# HSTF_SMD_V20.net
KiCad netlist of a schematic drawn in EAGLE
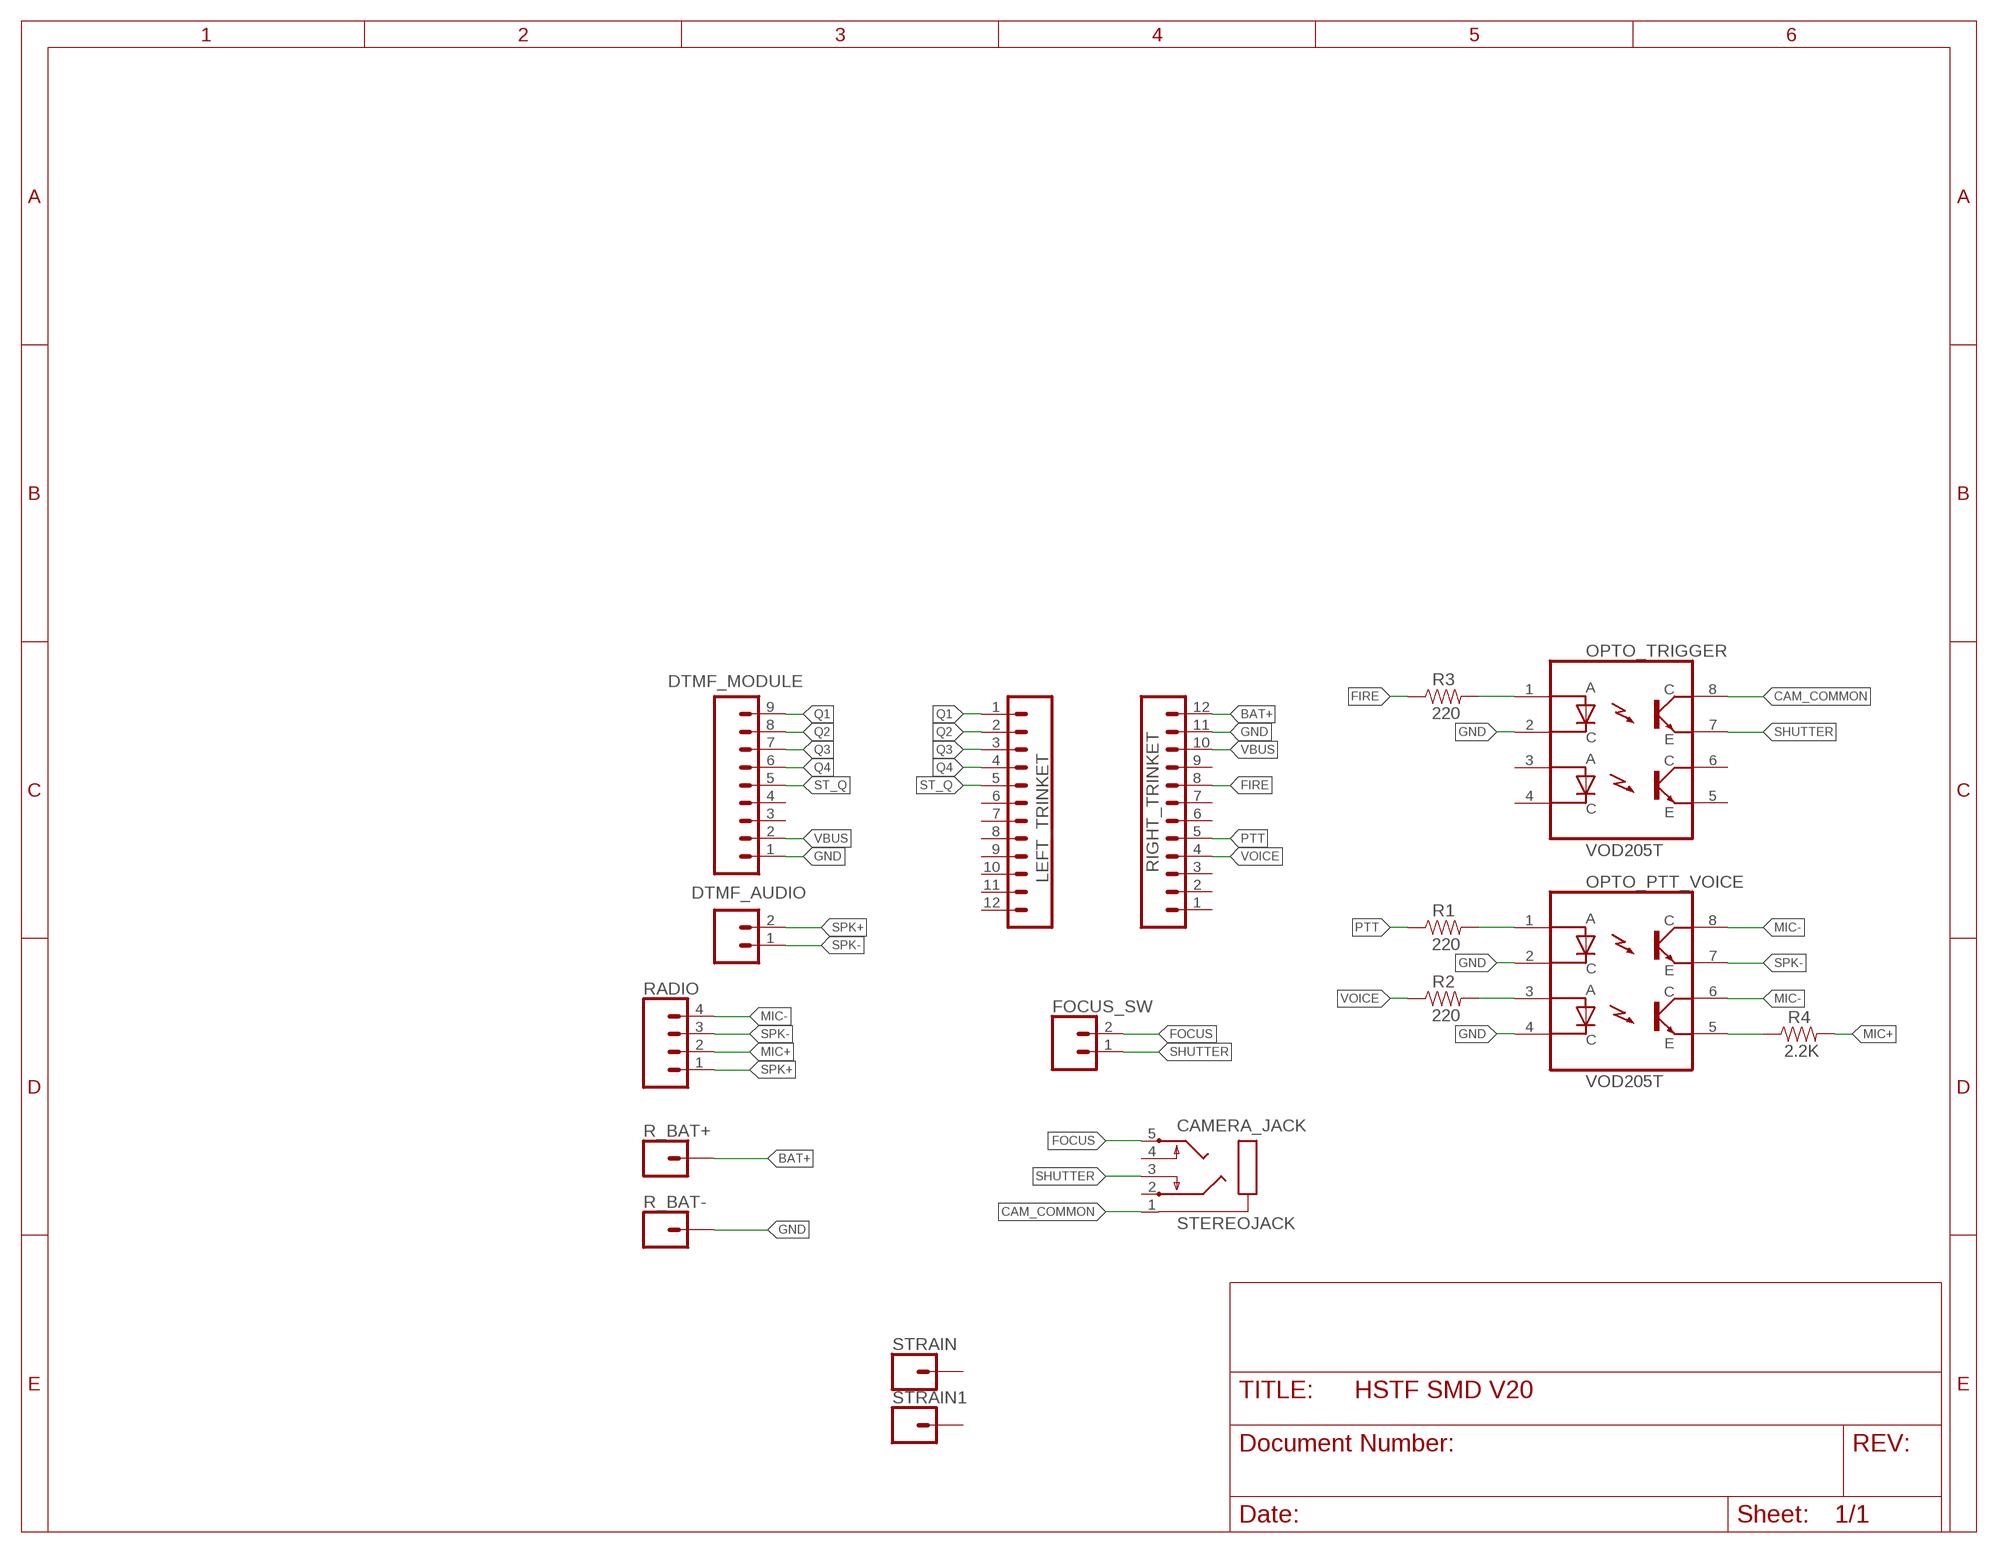
[diagram p0: schematic, sheet 1]

(export (version "E")
  (design (tool "Eeschema 10.0.6"))
  (components
    (comp (ref "CAMERA_JACK")
      (value "STEREOJACK")
      (footprint "eagle-import:STX3100")
      (libsource (lib "eagle-import") (part "STEREOJACK"))
    )
    (comp (ref "DTMF_AUDIO")
      (value "CONN_021X02_NO_SILK")
      (footprint "eagle-import:1X02_NO_SILK")
      (libsource (lib "eagle-import") (part "CONN_021X02_NO_SILK"))
    )
    (comp (ref "DTMF_MODULE")
      (value "CONN_09NO_SILK")
      (footprint "eagle-import:1X09_NO_SILK")
      (libsource (lib "eagle-import") (part "CONN_09NO_SILK"))
    )
    (comp (ref "FOCUS_SW")
      (value "CONN_021X02_NO_SILK")
      (footprint "eagle-import:1X02_NO_SILK")
      (libsource (lib "eagle-import") (part "CONN_021X02_NO_SILK"))
    )
    (comp (ref "LEFT_TRINKET")
      (value "CONN_12NO_SILK")
      (footprint "eagle-import:1X12_NO_SILK")
      (libsource (lib "eagle-import") (part "CONN_12NO_SILK"))
    )
    (comp (ref "OPTO_PTT_VOICE")
      (value "VOD205T")
      (footprint "eagle-import:SOIC127P610X331-8N")
      (fields (field (name "DIGI-KEY_PART_NUMBER") "VOD205TCT-ND") (field (name "MF") "Vishay Semiconductor"))
      (libsource (lib "eagle-import") (part "VOD205T"))
    )
    (comp (ref "OPTO_TRIGGER")
      (value "VOD205T")
      (footprint "eagle-import:SOIC127P610X331-8N")
      (fields (field (name "DIGI-KEY_PART_NUMBER") "VOD205TCT-ND") (field (name "MF") "Vishay Semiconductor"))
      (libsource (lib "eagle-import") (part "VOD205T"))
    )
    (comp (ref "R1")
      (value "220")
      (footprint "eagle-import:0805")
      (libsource (lib "eagle-import") (part "RESISTOR0805"))
    )
    (comp (ref "R2")
      (value "220")
      (footprint "eagle-import:0805")
      (libsource (lib "eagle-import") (part "RESISTOR0805"))
    )
    (comp (ref "R3")
      (value "220")
      (footprint "eagle-import:0805")
      (libsource (lib "eagle-import") (part "RESISTOR0805"))
    )
    (comp (ref "R4")
      (value "2.2K")
      (footprint "eagle-import:0805")
      (libsource (lib "eagle-import") (part "RESISTOR0805"))
    )
    (comp (ref "RADIO")
      (value "CONN_04LONGPADS")
      (footprint "eagle-import:1X04_LONGPADS")
      (libsource (lib "eagle-import") (part "CONN_04LONGPADS"))
    )
    (comp (ref "RIGHT_TRINKET")
      (value "CONN_12NO_SILK")
      (footprint "eagle-import:1X12_NO_SILK")
      (libsource (lib "eagle-import") (part "CONN_12NO_SILK"))
    )
    (comp (ref "R_BAT+")
      (value "CONN_01")
      (footprint "eagle-import:1X01")
      (libsource (lib "eagle-import") (part "CONN_01"))
    )
    (comp (ref "R_BAT-")
      (value "CONN_01")
      (footprint "eagle-import:1X01")
      (libsource (lib "eagle-import") (part "CONN_01"))
    )
    (comp (ref "STRAIN")
      (value "CONN_01")
      (footprint "eagle-import:1X01")
      (libsource (lib "eagle-import") (part "CONN_01"))
    )
    (comp (ref "STRAIN1")
      (value "CONN_01")
      (footprint "eagle-import:1X01")
      (libsource (lib "eagle-import") (part "CONN_01"))
    )
  )
  (nets
    (net (code "1") (name "BAT+") (class "Default")
      (node (ref "RIGHT_TRINKET") (pin "12") (pinfunction "12_12") (pintype "passive"))
      (node (ref "R_BAT+") (pin "1") (pinfunction "1_1") (pintype "passive"))
    )
    (net (code "2") (name "CAM_COMMON") (class "Default")
      (node (ref "CAMERA_JACK") (pin "1") (pinfunction "1_1") (pintype "passive"))
      (node (ref "OPTO_TRIGGER") (pin "8") (pinfunction "CO2_8") (pintype "passive"))
    )
    (net (code "3") (name "FIRE") (class "Default")
      (node (ref "R3") (pin "1") (pinfunction "1_1") (pintype "passive"))
      (node (ref "RIGHT_TRINKET") (pin "8") (pinfunction "8_8") (pintype "passive"))
    )
    (net (code "4") (name "FOCUS") (class "Default")
      (node (ref "CAMERA_JACK") (pin "5") (pinfunction "5_5") (pintype "passive"))
      (node (ref "FOCUS_SW") (pin "2") (pinfunction "2_2") (pintype "passive"))
    )
    (net (code "5") (name "GND") (class "Default")
      (node (ref "DTMF_MODULE") (pin "1") (pinfunction "1_1") (pintype "passive"))
      (node (ref "OPTO_PTT_VOICE") (pin "2") (pinfunction "C1_2") (pintype "passive"))
      (node (ref "OPTO_PTT_VOICE") (pin "4") (pinfunction "C2_4") (pintype "passive"))
      (node (ref "OPTO_TRIGGER") (pin "2") (pinfunction "C1_2") (pintype "passive"))
      (node (ref "RIGHT_TRINKET") (pin "11") (pinfunction "11_11") (pintype "passive"))
      (node (ref "R_BAT-") (pin "1") (pinfunction "1_1") (pintype "passive"))
    )
    (net (code "6") (name "MIC+") (class "Default")
      (node (ref "R4") (pin "2") (pinfunction "2_2") (pintype "passive"))
      (node (ref "RADIO") (pin "2") (pinfunction "2_2") (pintype "passive"))
    )
    (net (code "7") (name "MIC-") (class "Default")
      (node (ref "OPTO_PTT_VOICE") (pin "6") (pinfunction "CO1_6") (pintype "passive"))
      (node (ref "OPTO_PTT_VOICE") (pin "8") (pinfunction "CO2_8") (pintype "passive"))
      (node (ref "RADIO") (pin "4") (pinfunction "4_4") (pintype "passive"))
    )
    (net (code "8") (name "Net-(OPTO_PTT_VOICE-A1)") (class "Default")
      (node (ref "OPTO_PTT_VOICE") (pin "1") (pinfunction "A1_1") (pintype "passive"))
      (node (ref "R1") (pin "2") (pinfunction "2_2") (pintype "passive"))
    )
    (net (code "9") (name "Net-(OPTO_PTT_VOICE-A2)") (class "Default")
      (node (ref "OPTO_PTT_VOICE") (pin "3") (pinfunction "A2_3") (pintype "passive"))
      (node (ref "R2") (pin "2") (pinfunction "2_2") (pintype "passive"))
    )
    (net (code "10") (name "Net-(OPTO_PTT_VOICE-E1)") (class "Default")
      (node (ref "OPTO_PTT_VOICE") (pin "5") (pinfunction "E1_5") (pintype "passive"))
      (node (ref "R4") (pin "1") (pinfunction "1_1") (pintype "passive"))
    )
    (net (code "11") (name "Net-(OPTO_TRIGGER-A1)") (class "Default")
      (node (ref "OPTO_TRIGGER") (pin "1") (pinfunction "A1_1") (pintype "passive"))
      (node (ref "R3") (pin "2") (pinfunction "2_2") (pintype "passive"))
    )
    (net (code "12") (name "PTT") (class "Default")
      (node (ref "R1") (pin "1") (pinfunction "1_1") (pintype "passive"))
      (node (ref "RIGHT_TRINKET") (pin "5") (pinfunction "5_5") (pintype "passive"))
    )
    (net (code "13") (name "Q1") (class "Default")
      (node (ref "DTMF_MODULE") (pin "9") (pinfunction "9_9") (pintype "passive"))
      (node (ref "LEFT_TRINKET") (pin "1") (pinfunction "1_1") (pintype "passive"))
    )
    (net (code "14") (name "Q2") (class "Default")
      (node (ref "DTMF_MODULE") (pin "8") (pinfunction "8_8") (pintype "passive"))
      (node (ref "LEFT_TRINKET") (pin "2") (pinfunction "2_2") (pintype "passive"))
    )
    (net (code "15") (name "Q3") (class "Default")
      (node (ref "DTMF_MODULE") (pin "7") (pinfunction "7_7") (pintype "passive"))
      (node (ref "LEFT_TRINKET") (pin "3") (pinfunction "3_3") (pintype "passive"))
    )
    (net (code "16") (name "Q4") (class "Default")
      (node (ref "DTMF_MODULE") (pin "6") (pinfunction "6_6") (pintype "passive"))
      (node (ref "LEFT_TRINKET") (pin "4") (pinfunction "4_4") (pintype "passive"))
    )
    (net (code "17") (name "SHUTTER") (class "Default")
      (node (ref "CAMERA_JACK") (pin "3") (pinfunction "3_3") (pintype "passive"))
      (node (ref "FOCUS_SW") (pin "1") (pinfunction "1_1") (pintype "passive"))
      (node (ref "OPTO_TRIGGER") (pin "7") (pinfunction "E2_7") (pintype "passive"))
    )
    (net (code "18") (name "SPK+") (class "Default")
      (node (ref "DTMF_AUDIO") (pin "2") (pinfunction "2_2") (pintype "passive"))
      (node (ref "RADIO") (pin "1") (pinfunction "1_1") (pintype "passive"))
    )
    (net (code "19") (name "SPK-") (class "Default")
      (node (ref "DTMF_AUDIO") (pin "1") (pinfunction "1_1") (pintype "passive"))
      (node (ref "OPTO_PTT_VOICE") (pin "7") (pinfunction "E2_7") (pintype "passive"))
      (node (ref "RADIO") (pin "3") (pinfunction "3_3") (pintype "passive"))
    )
    (net (code "20") (name "ST_Q") (class "Default")
      (node (ref "DTMF_MODULE") (pin "5") (pinfunction "5_5") (pintype "passive"))
      (node (ref "LEFT_TRINKET") (pin "5") (pinfunction "5_5") (pintype "passive"))
    )
    (net (code "21") (name "VBUS") (class "Default")
      (node (ref "DTMF_MODULE") (pin "2") (pinfunction "2_2") (pintype "passive"))
      (node (ref "RIGHT_TRINKET") (pin "10") (pinfunction "10_10") (pintype "passive"))
    )
    (net (code "22") (name "VOICE") (class "Default")
      (node (ref "R2") (pin "1") (pinfunction "1_1") (pintype "passive"))
      (node (ref "RIGHT_TRINKET") (pin "4") (pinfunction "4_4") (pintype "passive"))
    )
    (net (code "23") (name "unconnected-(CAMERA_JACK-Pad2)") (class "Default")
      (node (ref "CAMERA_JACK") (pin "2") (pinfunction "2_2") (pintype "passive"))
    )
    (net (code "24") (name "unconnected-(CAMERA_JACK-Pad4)") (class "Default")
      (node (ref "CAMERA_JACK") (pin "4") (pinfunction "4_4") (pintype "passive"))
    )
    (net (code "25") (name "unconnected-(DTMF_MODULE-Pad3)") (class "Default")
      (node (ref "DTMF_MODULE") (pin "3") (pinfunction "3_3") (pintype "passive"))
    )
    (net (code "26") (name "unconnected-(DTMF_MODULE-Pad4)") (class "Default")
      (node (ref "DTMF_MODULE") (pin "4") (pinfunction "4_4") (pintype "passive"))
    )
    (net (code "27") (name "unconnected-(LEFT_TRINKET-Pad6)") (class "Default")
      (node (ref "LEFT_TRINKET") (pin "6") (pinfunction "6_6") (pintype "passive"))
    )
    (net (code "28") (name "unconnected-(LEFT_TRINKET-Pad7)") (class "Default")
      (node (ref "LEFT_TRINKET") (pin "7") (pinfunction "7_7") (pintype "passive"))
    )
    (net (code "29") (name "unconnected-(LEFT_TRINKET-Pad8)") (class "Default")
      (node (ref "LEFT_TRINKET") (pin "8") (pinfunction "8_8") (pintype "passive"))
    )
    (net (code "30") (name "unconnected-(LEFT_TRINKET-Pad9)") (class "Default")
      (node (ref "LEFT_TRINKET") (pin "9") (pinfunction "9_9") (pintype "passive"))
    )
    (net (code "31") (name "unconnected-(LEFT_TRINKET-Pad10)") (class "Default")
      (node (ref "LEFT_TRINKET") (pin "10") (pinfunction "10_10") (pintype "passive"))
    )
    (net (code "32") (name "unconnected-(LEFT_TRINKET-Pad11)") (class "Default")
      (node (ref "LEFT_TRINKET") (pin "11") (pinfunction "11_11") (pintype "passive"))
    )
    (net (code "33") (name "unconnected-(LEFT_TRINKET-Pad12)") (class "Default")
      (node (ref "LEFT_TRINKET") (pin "12") (pinfunction "12_12") (pintype "passive"))
    )
    (net (code "34") (name "unconnected-(OPTO_TRIGGER-A2-Pad3)") (class "Default")
      (node (ref "OPTO_TRIGGER") (pin "3") (pinfunction "A2_3") (pintype "passive"))
    )
    (net (code "35") (name "unconnected-(OPTO_TRIGGER-C2-Pad4)") (class "Default")
      (node (ref "OPTO_TRIGGER") (pin "4") (pinfunction "C2_4") (pintype "passive"))
    )
    (net (code "36") (name "unconnected-(OPTO_TRIGGER-CO1-Pad6)") (class "Default")
      (node (ref "OPTO_TRIGGER") (pin "6") (pinfunction "CO1_6") (pintype "passive"))
    )
    (net (code "37") (name "unconnected-(OPTO_TRIGGER-E1-Pad5)") (class "Default")
      (node (ref "OPTO_TRIGGER") (pin "5") (pinfunction "E1_5") (pintype "passive"))
    )
    (net (code "38") (name "unconnected-(RIGHT_TRINKET-Pad1)") (class "Default")
      (node (ref "RIGHT_TRINKET") (pin "1") (pinfunction "1_1") (pintype "passive"))
    )
    (net (code "39") (name "unconnected-(RIGHT_TRINKET-Pad2)") (class "Default")
      (node (ref "RIGHT_TRINKET") (pin "2") (pinfunction "2_2") (pintype "passive"))
    )
    (net (code "40") (name "unconnected-(RIGHT_TRINKET-Pad3)") (class "Default")
      (node (ref "RIGHT_TRINKET") (pin "3") (pinfunction "3_3") (pintype "passive"))
    )
    (net (code "41") (name "unconnected-(RIGHT_TRINKET-Pad6)") (class "Default")
      (node (ref "RIGHT_TRINKET") (pin "6") (pinfunction "6_6") (pintype "passive"))
    )
    (net (code "42") (name "unconnected-(RIGHT_TRINKET-Pad7)") (class "Default")
      (node (ref "RIGHT_TRINKET") (pin "7") (pinfunction "7_7") (pintype "passive"))
    )
    (net (code "43") (name "unconnected-(RIGHT_TRINKET-Pad9)") (class "Default")
      (node (ref "RIGHT_TRINKET") (pin "9") (pinfunction "9_9") (pintype "passive"))
    )
    (net (code "44") (name "unconnected-(STRAIN-Pad1)") (class "Default")
      (node (ref "STRAIN") (pin "1") (pinfunction "1_1") (pintype "passive"))
    )
    (net (code "45") (name "unconnected-(STRAIN1-Pad1)") (class "Default")
      (node (ref "STRAIN1") (pin "1") (pinfunction "1_1") (pintype "passive"))
    )
  )
)
